# pira-badge-attiny3.net
KiCad netlist of a schematic drawn in EAGLE
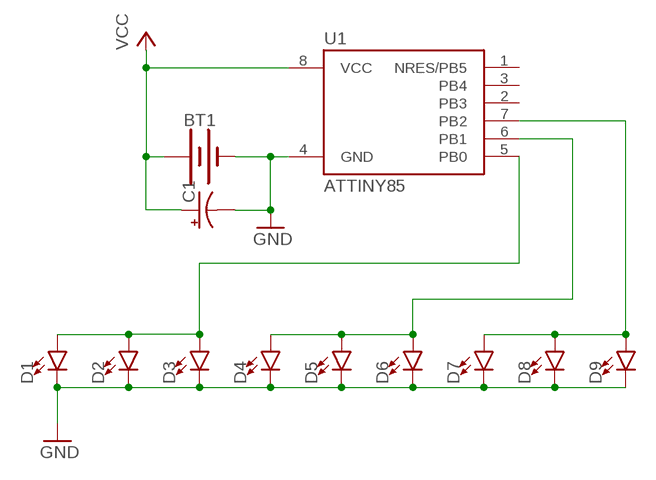
[diagram p0: schematic, sheet 1]

(export (version "E")
  (design (tool "Eeschema 10.0.6"))
  (components
    (comp (ref "BT1")
      (value "BATTERY-24.5MM_PTH")
      (footprint "eagle-import:BATTCON_24.5MM_PTH")
      (libsource (lib "eagle-import") (part "BATTERY-24.5MM_PTH"))
    )
    (comp (ref "C1")
      (value "CPOL-USCT3216")
      (footprint "eagle-import:CT3216")
      (libsource (lib "eagle-import") (part "CPOL-USCT3216"))
    )
    (comp (ref "D1")
      (value "LED1206")
      (footprint "eagle-import:LED-1206")
      (libsource (lib "eagle-import") (part "LED1206"))
    )
    (comp (ref "D2")
      (value "LED1206")
      (footprint "eagle-import:LED-1206")
      (libsource (lib "eagle-import") (part "LED1206"))
    )
    (comp (ref "D3")
      (value "LED1206")
      (footprint "eagle-import:LED-1206")
      (libsource (lib "eagle-import") (part "LED1206"))
    )
    (comp (ref "D4")
      (value "LED1206")
      (footprint "eagle-import:LED-1206")
      (libsource (lib "eagle-import") (part "LED1206"))
    )
    (comp (ref "D5")
      (value "LED1206")
      (footprint "eagle-import:LED-1206")
      (libsource (lib "eagle-import") (part "LED1206"))
    )
    (comp (ref "D6")
      (value "LED1206")
      (footprint "eagle-import:LED-1206")
      (libsource (lib "eagle-import") (part "LED1206"))
    )
    (comp (ref "D7")
      (value "LED1206")
      (footprint "eagle-import:LED-1206")
      (libsource (lib "eagle-import") (part "LED1206"))
    )
    (comp (ref "D8")
      (value "LED1206")
      (footprint "eagle-import:LED-1206")
      (libsource (lib "eagle-import") (part "LED1206"))
    )
    (comp (ref "D9")
      (value "LED1206")
      (footprint "eagle-import:LED-1206")
      (libsource (lib "eagle-import") (part "LED1206"))
    )
    (comp (ref "U1")
      (value "ATTINY85")
      (footprint "eagle-import:SOIC8_EIAJ_208MIL")
      (libsource (lib "eagle-import") (part "ATTINY85S-20"))
    )
  )
  (nets
    (net (code "1") (name "GND") (class "Default")
      (node (ref "BT1") (pin "2") (pinfunction "-_2") (pintype "power_in"))
      (node (ref "C1") (pin "-") (pinfunction "-_-") (pintype "passive"))
      (node (ref "D1") (pin "C") (pinfunction "C_C") (pintype "passive"))
      (node (ref "D2") (pin "C") (pinfunction "C_C") (pintype "passive"))
      (node (ref "D3") (pin "C") (pinfunction "C_C") (pintype "passive"))
      (node (ref "D4") (pin "C") (pinfunction "C_C") (pintype "passive"))
      (node (ref "D5") (pin "C") (pinfunction "C_C") (pintype "passive"))
      (node (ref "D6") (pin "C") (pinfunction "C_C") (pintype "passive"))
      (node (ref "D7") (pin "C") (pinfunction "C_C") (pintype "passive"))
      (node (ref "D8") (pin "C") (pinfunction "C_C") (pintype "passive"))
      (node (ref "D9") (pin "C") (pinfunction "C_C") (pintype "passive"))
      (node (ref "U1") (pin "4") (pinfunction "GND_4") (pintype "power_in"))
    )
    (net (code "2") (name "Net-(U1-PB0)") (class "Default")
      (node (ref "D1") (pin "A") (pinfunction "A_A") (pintype "passive"))
      (node (ref "D2") (pin "A") (pinfunction "A_A") (pintype "passive"))
      (node (ref "D3") (pin "A") (pinfunction "A_A") (pintype "passive"))
      (node (ref "U1") (pin "5") (pinfunction "PB0_5") (pintype "bidirectional"))
    )
    (net (code "3") (name "Net-(U1-PB1)") (class "Default")
      (node (ref "D4") (pin "A") (pinfunction "A_A") (pintype "passive"))
      (node (ref "D5") (pin "A") (pinfunction "A_A") (pintype "passive"))
      (node (ref "D6") (pin "A") (pinfunction "A_A") (pintype "passive"))
      (node (ref "U1") (pin "6") (pinfunction "PB1_6") (pintype "bidirectional"))
    )
    (net (code "4") (name "Net-(U1-PB2)") (class "Default")
      (node (ref "D7") (pin "A") (pinfunction "A_A") (pintype "passive"))
      (node (ref "D8") (pin "A") (pinfunction "A_A") (pintype "passive"))
      (node (ref "D9") (pin "A") (pinfunction "A_A") (pintype "passive"))
      (node (ref "U1") (pin "7") (pinfunction "PB2_7") (pintype "bidirectional"))
    )
    (net (code "5") (name "VCC") (class "Default")
      (node (ref "BT1") (pin "3") (pinfunction "+_3") (pintype "power_in"))
      (node (ref "C1") (pin "+") (pinfunction "+_+") (pintype "passive"))
      (node (ref "U1") (pin "8") (pinfunction "VCC_8") (pintype "power_in"))
    )
    (net (code "6") (name "unconnected-(U1-NRES{slash}PB5-Pad1)") (class "Default")
      (node (ref "U1") (pin "1") (pinfunction "NRES/PB5_1") (pintype "bidirectional"))
    )
    (net (code "7") (name "unconnected-(U1-PB3-Pad2)") (class "Default")
      (node (ref "U1") (pin "2") (pinfunction "PB3_2") (pintype "bidirectional"))
    )
    (net (code "8") (name "unconnected-(U1-PB4-Pad3)") (class "Default")
      (node (ref "U1") (pin "3") (pinfunction "PB4_3") (pintype "bidirectional"))
    )
  )
)
